# maddomat-master.net
KiCad netlist of a schematic drawn in EAGLE
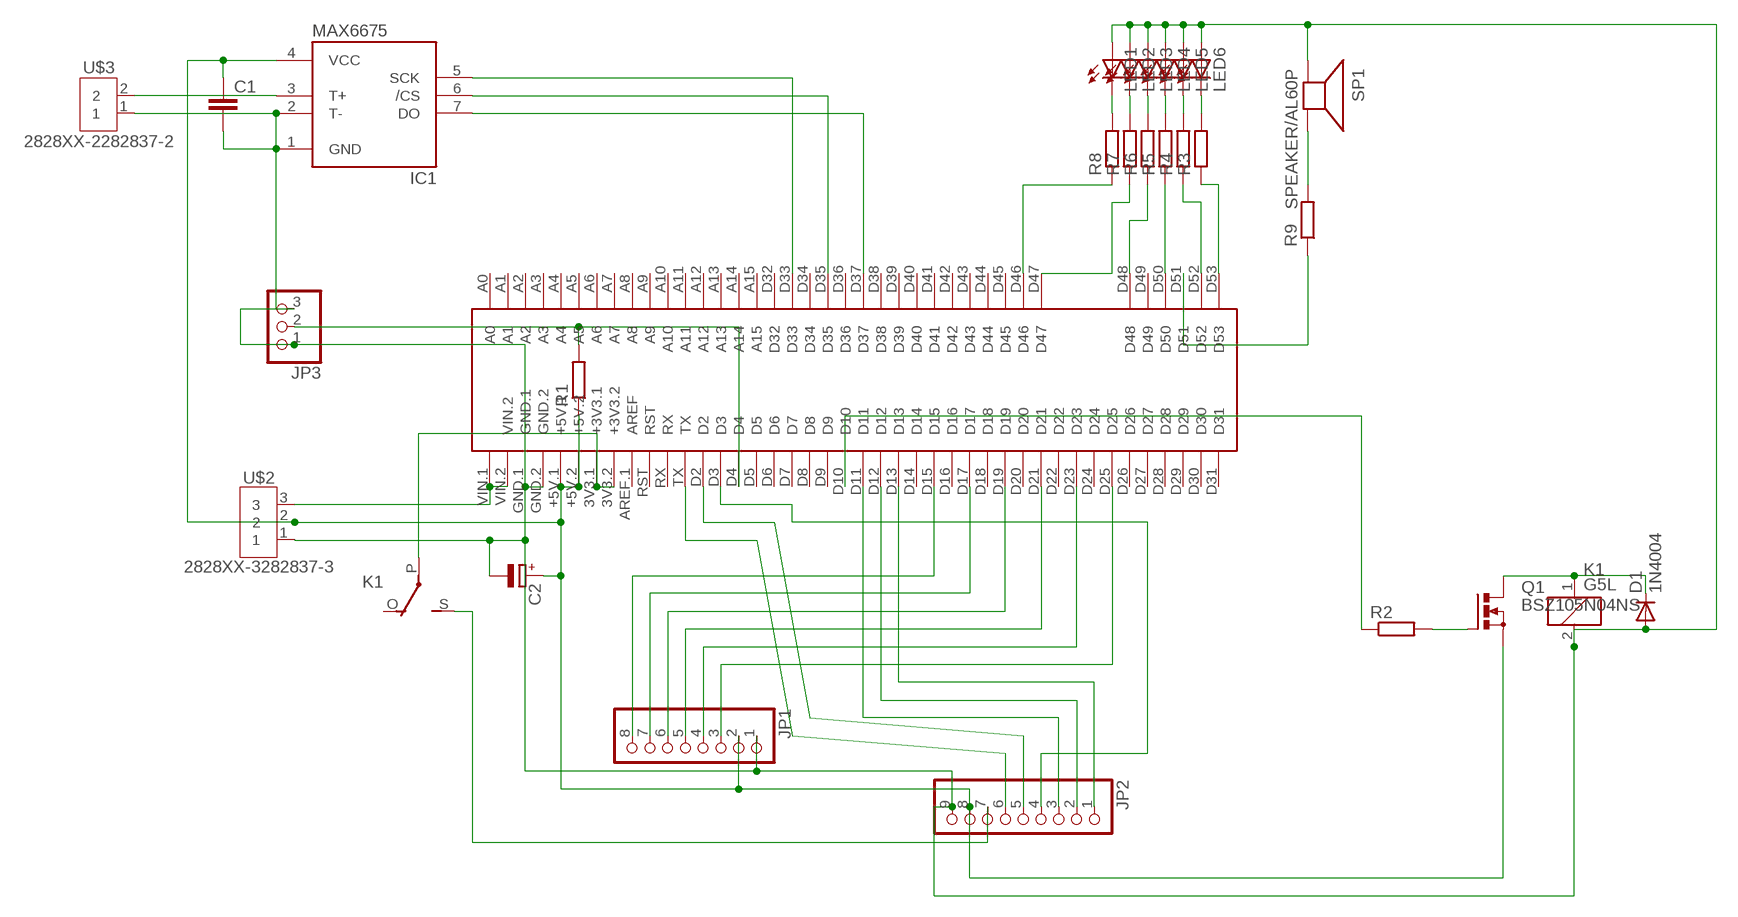
[diagram p0: schematic, sheet 1]

(export (version "E")
  (design (tool "Eeschema 10.0.6"))
  (components
    (comp (ref "C1")
      (value "C-EUC0805")
      (footprint "eagle-import:C0805")
      (libsource (lib "eagle-import") (part "C-EUC0805"))
    )
    (comp (ref "C2")
      (value "CPOL-EUE5-10.5")
      (footprint "eagle-import:E5-10,5")
      (libsource (lib "eagle-import") (part "CPOL-EUE5-10.5"))
    )
    (comp (ref "D1")
      (value "1N4004")
      (footprint "eagle-import:DO41-10")
      (libsource (lib "eagle-import") (part "1N4004"))
    )
    (comp (ref "IC1")
      (value "MAX6675")
      (footprint "eagle-import:SO08")
      (libsource (lib "eagle-import") (part "MAX6675"))
    )
    (comp (ref "JP1")
      (value "PINHD-1X8")
      (footprint "eagle-import:1X08")
      (libsource (lib "eagle-import") (part "PINHD-1X8"))
    )
    (comp (ref "JP2")
      (value "PINHD-1X9")
      (footprint "eagle-import:1X09")
      (libsource (lib "eagle-import") (part "PINHD-1X9"))
    )
    (comp (ref "JP3")
      (value "PINHD-1X3")
      (footprint "eagle-import:1X03")
      (libsource (lib "eagle-import") (part "PINHD-1X3"))
    )
    (comp (ref "K1")
      (value "G5L")
      (footprint "eagle-import:G5LE")
      (libsource (lib "eagle-import") (part "G5L"))
    )
    (comp (ref "LED1")
      (value "LEDCHIP-LED0805")
      (footprint "eagle-import:CHIP-LED0805")
      (libsource (lib "eagle-import") (part "LEDCHIP-LED0805"))
    )
    (comp (ref "LED2")
      (value "LEDCHIP-LED0805")
      (footprint "eagle-import:CHIP-LED0805")
      (libsource (lib "eagle-import") (part "LEDCHIP-LED0805"))
    )
    (comp (ref "LED3")
      (value "LEDCHIP-LED0805")
      (footprint "eagle-import:CHIP-LED0805")
      (libsource (lib "eagle-import") (part "LEDCHIP-LED0805"))
    )
    (comp (ref "LED4")
      (value "LEDCHIP-LED0805")
      (footprint "eagle-import:CHIP-LED0805")
      (libsource (lib "eagle-import") (part "LEDCHIP-LED0805"))
    )
    (comp (ref "LED5")
      (value "LEDCHIP-LED0805")
      (footprint "eagle-import:CHIP-LED0805")
      (libsource (lib "eagle-import") (part "LEDCHIP-LED0805"))
    )
    (comp (ref "LED6")
      (value "LEDCHIP-LED0805")
      (footprint "eagle-import:CHIP-LED0805")
      (libsource (lib "eagle-import") (part "LEDCHIP-LED0805"))
    )
    (comp (ref "Q1")
      (value "BSZ105N04NS")
      (footprint "eagle-import:PG-TDSON-8")
      (libsource (lib "eagle-import") (part "BSZ105N04NS"))
    )
    (comp (ref "R1")
      (value "R-EU_M0805")
      (footprint "eagle-import:M0805")
      (libsource (lib "eagle-import") (part "R-EU_M0805"))
    )
    (comp (ref "R2")
      (value "R-EU_M0805")
      (footprint "eagle-import:M0805")
      (libsource (lib "eagle-import") (part "R-EU_M0805"))
    )
    (comp (ref "R3")
      (value "R-EU_M0805")
      (footprint "eagle-import:M0805")
      (libsource (lib "eagle-import") (part "R-EU_M0805"))
    )
    (comp (ref "R4")
      (value "R-EU_M0805")
      (footprint "eagle-import:M0805")
      (libsource (lib "eagle-import") (part "R-EU_M0805"))
    )
    (comp (ref "R5")
      (value "R-EU_M0805")
      (footprint "eagle-import:M0805")
      (libsource (lib "eagle-import") (part "R-EU_M0805"))
    )
    (comp (ref "R6")
      (value "R-EU_M0805")
      (footprint "eagle-import:M0805")
      (libsource (lib "eagle-import") (part "R-EU_M0805"))
    )
    (comp (ref "R7")
      (value "R-EU_M0805")
      (footprint "eagle-import:M0805")
      (libsource (lib "eagle-import") (part "R-EU_M0805"))
    )
    (comp (ref "R8")
      (value "R-EU_M0805")
      (footprint "eagle-import:M0805")
      (libsource (lib "eagle-import") (part "R-EU_M0805"))
    )
    (comp (ref "R9")
      (value "R-EU_M0805")
      (footprint "eagle-import:M0805")
      (libsource (lib "eagle-import") (part "R-EU_M0805"))
    )
    (comp (ref "SP1")
      (value "SPEAKER/AL60P")
      (footprint "eagle-import:AL60P")
      (libsource (lib "eagle-import") (part "SPEAKER/AL60P"))
    )
    (comp (ref "U$1")
      (value "MEGA2560_MIKRO")
      (footprint "eagle-import:MEGA2560_MIKRO")
      (libsource (lib "eagle-import") (part "MEGA2560_MIKRO"))
    )
    (comp (ref "U$2")
      (value "2828XX-3282837-3")
      (footprint "eagle-import:TERMBLK_508-3N")
      (fields (field (name "MANUFACTURER") "TE Connectivity") (field (name "MPN") "282837-3"))
      (libsource (lib "eagle-import") (part "2828XX-3282837-3"))
    )
    (comp (ref "U$3")
      (value "2828XX-2282837-2")
      (footprint "eagle-import:TERMBLK_508-2N")
      (fields (field (name "MANUFACTURER") "TE Connectivity") (field (name "MPN") "282837-2"))
      (libsource (lib "eagle-import") (part "2828XX-2282837-2"))
    )
  )
  (nets
    (net (code "1") (name "Net-(D1-PadC)") (class "Default")
      (node (ref "D1") (pin "C") (pinfunction "C_C") (pintype "passive"))
      (node (ref "K1") (pin "1") (pinfunction "1_1") (pintype "passive"))
      (node (ref "Q1") (pin "5") (pinfunction "D_5") (pintype "passive"))
      (node (ref "Q1") (pin "6") (pinfunction "D_6") (pintype "passive"))
      (node (ref "Q1") (pin "7") (pinfunction "D_7") (pintype "passive"))
      (node (ref "Q1") (pin "8") (pinfunction "D_8") (pintype "passive"))
      (node (ref "Q1") (pin "TH") (pinfunction "D_TH") (pintype "passive"))
    )
    (net (code "2") (name "Net-(IC1-DO)") (class "Default")
      (node (ref "IC1") (pin "7") (pinfunction "DO_7") (pintype "output"))
      (node (ref "U$1") (pin "D37") (pinfunction "D37_D37") (pintype "bidirectional"))
    )
    (net (code "3") (name "Net-(IC1-GND)") (class "Default")
      (node (ref "C1") (pin "2") (pinfunction "2_2") (pintype "passive"))
      (node (ref "C2") (pin "-") (pinfunction "-_-") (pintype "passive"))
      (node (ref "D1") (pin "A") (pinfunction "A_A") (pintype "passive"))
      (node (ref "IC1") (pin "1") (pinfunction "GND_1") (pintype "power_in"))
      (node (ref "IC1") (pin "2") (pinfunction "T-_2") (pintype "input"))
      (node (ref "JP1") (pin "1") (pinfunction "1_1") (pintype "passive"))
      (node (ref "JP2") (pin "9") (pinfunction "9_9") (pintype "passive"))
      (node (ref "JP3") (pin "1") (pinfunction "1_1") (pintype "passive"))
      (node (ref "JP3") (pin "3") (pinfunction "3_3") (pintype "passive"))
      (node (ref "K1") (pin "2") (pinfunction "2_2") (pintype "passive"))
      (node (ref "LED1") (pin "A") (pinfunction "A_A") (pintype "passive"))
      (node (ref "LED2") (pin "A") (pinfunction "A_A") (pintype "passive"))
      (node (ref "LED3") (pin "A") (pinfunction "A_A") (pintype "passive"))
      (node (ref "LED4") (pin "A") (pinfunction "A_A") (pintype "passive"))
      (node (ref "LED5") (pin "A") (pinfunction "A_A") (pintype "passive"))
      (node (ref "LED6") (pin "A") (pinfunction "A_A") (pintype "passive"))
      (node (ref "SP1") (pin "1") (pinfunction "+_1") (pintype "passive"))
      (node (ref "U$1") (pin "GND.1") (pinfunction "GND.1_GND.1") (pintype "bidirectional"))
      (node (ref "U$1") (pin "GND.2") (pinfunction "GND.2_GND.2") (pintype "bidirectional"))
      (node (ref "U$2") (pin "1") (pinfunction "1_1") (pintype "bidirectional"))
      (node (ref "U$3") (pin "1") (pinfunction "1_1") (pintype "bidirectional"))
    )
    (net (code "4") (name "Net-(IC1-SCK)") (class "Default")
      (node (ref "IC1") (pin "5") (pinfunction "SCK_5") (pintype "input"))
      (node (ref "U$1") (pin "D33") (pinfunction "D33_D33") (pintype "bidirectional"))
    )
    (net (code "5") (name "Net-(IC1-T+)") (class "Default")
      (node (ref "IC1") (pin "3") (pinfunction "T+_3") (pintype "input"))
      (node (ref "U$3") (pin "2") (pinfunction "2_2") (pintype "bidirectional"))
    )
    (net (code "6") (name "Net-(IC1-VCC)") (class "Default")
      (node (ref "C1") (pin "1") (pinfunction "1_1") (pintype "passive"))
      (node (ref "C2") (pin "+") (pinfunction "+_+") (pintype "passive"))
      (node (ref "IC1") (pin "4") (pinfunction "VCC_4") (pintype "power_in"))
      (node (ref "JP1") (pin "2") (pinfunction "2_2") (pintype "passive"))
      (node (ref "JP2") (pin "8") (pinfunction "8_8") (pintype "passive"))
      (node (ref "Q1") (pin "1") (pinfunction "S_1") (pintype "passive"))
      (node (ref "Q1") (pin "2") (pinfunction "S_2") (pintype "passive"))
      (node (ref "Q1") (pin "3") (pinfunction "S_3") (pintype "passive"))
      (node (ref "R1") (pin "1") (pinfunction "1_1") (pintype "passive"))
      (node (ref "U$1") (pin "+5V.1") (pinfunction "+5V.1_+5V.1") (pintype "bidirectional"))
      (node (ref "U$1") (pin "+5V.2") (pinfunction "+5V.2_+5V.2") (pintype "bidirectional"))
      (node (ref "U$2") (pin "2") (pinfunction "2_2") (pintype "bidirectional"))
    )
    (net (code "7") (name "Net-(IC1-{slash}CS)") (class "Default")
      (node (ref "IC1") (pin "6") (pinfunction "/CS_6") (pintype "input"))
      (node (ref "U$1") (pin "D35") (pinfunction "D35_D35") (pintype "bidirectional"))
    )
    (net (code "8") (name "Net-(JP1-Pad3)") (class "Default")
      (node (ref "JP1") (pin "3") (pinfunction "3_3") (pintype "passive"))
      (node (ref "U$1") (pin "D25") (pinfunction "D25_D25") (pintype "bidirectional"))
    )
    (net (code "9") (name "Net-(JP1-Pad4)") (class "Default")
      (node (ref "JP1") (pin "4") (pinfunction "4_4") (pintype "passive"))
      (node (ref "U$1") (pin "D23") (pinfunction "D23_D23") (pintype "bidirectional"))
    )
    (net (code "10") (name "Net-(JP1-Pad5)") (class "Default")
      (node (ref "JP1") (pin "5") (pinfunction "5_5") (pintype "passive"))
      (node (ref "U$1") (pin "D21") (pinfunction "D21_D21") (pintype "bidirectional"))
    )
    (net (code "11") (name "Net-(JP1-Pad6)") (class "Default")
      (node (ref "JP1") (pin "6") (pinfunction "6_6") (pintype "passive"))
      (node (ref "U$1") (pin "D19") (pinfunction "D19_D19") (pintype "bidirectional"))
    )
    (net (code "12") (name "Net-(JP1-Pad7)") (class "Default")
      (node (ref "JP1") (pin "7") (pinfunction "7_7") (pintype "passive"))
      (node (ref "U$1") (pin "D17") (pinfunction "D17_D17") (pintype "bidirectional"))
    )
    (net (code "13") (name "Net-(JP1-Pad8)") (class "Default")
      (node (ref "JP1") (pin "8") (pinfunction "8_8") (pintype "passive"))
      (node (ref "U$1") (pin "D15") (pinfunction "D15_D15") (pintype "bidirectional"))
    )
    (net (code "14") (name "Net-(JP2-Pad1)") (class "Default")
      (node (ref "JP2") (pin "1") (pinfunction "1_1") (pintype "passive"))
      (node (ref "U$1") (pin "D13") (pinfunction "D13_D13") (pintype "bidirectional"))
    )
    (net (code "15") (name "Net-(JP2-Pad2)") (class "Default")
      (node (ref "JP2") (pin "2") (pinfunction "2_2") (pintype "passive"))
      (node (ref "U$1") (pin "D12") (pinfunction "D12_D12") (pintype "bidirectional"))
    )
    (net (code "16") (name "Net-(JP2-Pad3)") (class "Default")
      (node (ref "JP2") (pin "3") (pinfunction "3_3") (pintype "passive"))
      (node (ref "U$1") (pin "D11") (pinfunction "D11_D11") (pintype "bidirectional"))
    )
    (net (code "17") (name "Net-(JP2-Pad4)") (class "Default")
      (node (ref "JP2") (pin "4") (pinfunction "4_4") (pintype "passive"))
      (node (ref "U$1") (pin "D3") (pinfunction "D3_D3") (pintype "bidirectional"))
    )
    (net (code "18") (name "Net-(JP2-Pad5)") (class "Default")
      (node (ref "JP2") (pin "5") (pinfunction "5_5") (pintype "passive"))
      (node (ref "U$1") (pin "D2") (pinfunction "D2_D2") (pintype "bidirectional"))
    )
    (net (code "19") (name "Net-(JP2-Pad6)") (class "Default")
      (node (ref "JP2") (pin "6") (pinfunction "6_6") (pintype "passive"))
      (node (ref "U$1") (pin "TX") (pinfunction "TX_TX") (pintype "bidirectional"))
    )
    (net (code "20") (name "Net-(JP2-Pad7)") (class "Default")
      (node (ref "JP2") (pin "7") (pinfunction "7_7") (pintype "passive"))
      (node (ref "K1") (pin "S") (pinfunction "S_S") (pintype "passive"))
    )
    (net (code "21") (name "Net-(JP3-Pad2)") (class "Default")
      (node (ref "JP3") (pin "2") (pinfunction "2_2") (pintype "passive"))
      (node (ref "R1") (pin "2") (pinfunction "2_2") (pintype "passive"))
      (node (ref "U$1") (pin "D4") (pinfunction "D4_D4") (pintype "bidirectional"))
    )
    (net (code "22") (name "Net-(LED1-PadC)") (class "Default")
      (node (ref "LED1") (pin "C") (pinfunction "C_C") (pintype "passive"))
      (node (ref "R8") (pin "2") (pinfunction "2_2") (pintype "passive"))
    )
    (net (code "23") (name "Net-(LED2-PadC)") (class "Default")
      (node (ref "LED2") (pin "C") (pinfunction "C_C") (pintype "passive"))
      (node (ref "R7") (pin "2") (pinfunction "2_2") (pintype "passive"))
    )
    (net (code "24") (name "Net-(LED3-PadC)") (class "Default")
      (node (ref "LED3") (pin "C") (pinfunction "C_C") (pintype "passive"))
      (node (ref "R6") (pin "2") (pinfunction "2_2") (pintype "passive"))
    )
    (net (code "25") (name "Net-(LED4-PadC)") (class "Default")
      (node (ref "LED4") (pin "C") (pinfunction "C_C") (pintype "passive"))
      (node (ref "R5") (pin "2") (pinfunction "2_2") (pintype "passive"))
    )
    (net (code "26") (name "Net-(LED5-PadC)") (class "Default")
      (node (ref "LED5") (pin "C") (pinfunction "C_C") (pintype "passive"))
      (node (ref "R4") (pin "2") (pinfunction "2_2") (pintype "passive"))
    )
    (net (code "27") (name "Net-(LED6-PadC)") (class "Default")
      (node (ref "LED6") (pin "C") (pinfunction "C_C") (pintype "passive"))
      (node (ref "R3") (pin "2") (pinfunction "2_2") (pintype "passive"))
    )
    (net (code "28") (name "Net-(Q1-G)") (class "Default")
      (node (ref "Q1") (pin "4") (pinfunction "G_4") (pintype "passive"))
      (node (ref "R2") (pin "2") (pinfunction "2_2") (pintype "passive"))
    )
    (net (code "29") (name "Net-(R2-Pad1)") (class "Default")
      (node (ref "R2") (pin "1") (pinfunction "1_1") (pintype "passive"))
      (node (ref "U$1") (pin "D10") (pinfunction "D10_D10") (pintype "bidirectional"))
    )
    (net (code "30") (name "Net-(R3-Pad1)") (class "Default")
      (node (ref "R3") (pin "1") (pinfunction "1_1") (pintype "passive"))
      (node (ref "U$1") (pin "D53") (pinfunction "D53_D53") (pintype "bidirectional"))
    )
    (net (code "31") (name "Net-(R4-Pad1)") (class "Default")
      (node (ref "R4") (pin "1") (pinfunction "1_1") (pintype "passive"))
      (node (ref "U$1") (pin "D52") (pinfunction "D52_D52") (pintype "bidirectional"))
    )
    (net (code "32") (name "Net-(R5-Pad1)") (class "Default")
      (node (ref "R5") (pin "1") (pinfunction "1_1") (pintype "passive"))
      (node (ref "U$1") (pin "D50") (pinfunction "D50_D50") (pintype "bidirectional"))
    )
    (net (code "33") (name "Net-(R6-Pad1)") (class "Default")
      (node (ref "R6") (pin "1") (pinfunction "1_1") (pintype "passive"))
      (node (ref "U$1") (pin "D48") (pinfunction "D48_D48") (pintype "bidirectional"))
    )
    (net (code "34") (name "Net-(R7-Pad1)") (class "Default")
      (node (ref "R7") (pin "1") (pinfunction "1_1") (pintype "passive"))
      (node (ref "U$1") (pin "D47") (pinfunction "D47_D47") (pintype "bidirectional"))
    )
    (net (code "35") (name "Net-(R8-Pad1)") (class "Default")
      (node (ref "R8") (pin "1") (pinfunction "1_1") (pintype "passive"))
      (node (ref "U$1") (pin "D46") (pinfunction "D46_D46") (pintype "bidirectional"))
    )
    (net (code "36") (name "Net-(R9-Pad1)") (class "Default")
      (node (ref "R9") (pin "1") (pinfunction "1_1") (pintype "passive"))
      (node (ref "U$1") (pin "D51") (pinfunction "D51_D51") (pintype "bidirectional"))
    )
    (net (code "37") (name "Net-(SP1--)") (class "Default")
      (node (ref "R9") (pin "2") (pinfunction "2_2") (pintype "passive"))
      (node (ref "SP1") (pin "2") (pinfunction "-_2") (pintype "passive"))
    )
    (net (code "38") (name "Net-(U$1-+3V3.1)") (class "Default")
      (node (ref "K1") (pin "P") (pinfunction "P_P") (pintype "passive"))
      (node (ref "U$1") (pin "3V3.1") (pinfunction "+3V3.1_3V3.1") (pintype "bidirectional"))
      (node (ref "U$1") (pin "3V3.2") (pinfunction "+3V3.2_3V3.2") (pintype "bidirectional"))
    )
    (net (code "39") (name "Net-(U$1-PadVIN.1)") (class "Default")
      (node (ref "U$1") (pin "VIN.1") (pinfunction "VIN.1_VIN.1") (pintype "bidirectional"))
      (node (ref "U$1") (pin "VIN.2") (pinfunction "VIN.2_VIN.2") (pintype "bidirectional"))
      (node (ref "U$2") (pin "3") (pinfunction "3_3") (pintype "bidirectional"))
    )
    (net (code "40") (name "unconnected-(K1-PadO)") (class "Default")
      (node (ref "K1") (pin "O") (pinfunction "O_O") (pintype "passive"))
    )
    (net (code "41") (name "unconnected-(U$1-AREF-PadAREF.1)") (class "Default")
      (node (ref "U$1") (pin "AREF.1") (pinfunction "AREF_AREF.1") (pintype "bidirectional"))
    )
    (net (code "42") (name "unconnected-(U$1-PadA0)") (class "Default")
      (node (ref "U$1") (pin "A0") (pinfunction "A0_A0") (pintype "bidirectional"))
    )
    (net (code "43") (name "unconnected-(U$1-PadA1)") (class "Default")
      (node (ref "U$1") (pin "A1") (pinfunction "A1_A1") (pintype "bidirectional"))
    )
    (net (code "44") (name "unconnected-(U$1-PadA2)") (class "Default")
      (node (ref "U$1") (pin "A2") (pinfunction "A2_A2") (pintype "bidirectional"))
    )
    (net (code "45") (name "unconnected-(U$1-PadA3)") (class "Default")
      (node (ref "U$1") (pin "A3") (pinfunction "A3_A3") (pintype "bidirectional"))
    )
    (net (code "46") (name "unconnected-(U$1-PadA4)") (class "Default")
      (node (ref "U$1") (pin "A4") (pinfunction "A4_A4") (pintype "bidirectional"))
    )
    (net (code "47") (name "unconnected-(U$1-PadA5)") (class "Default")
      (node (ref "U$1") (pin "A5") (pinfunction "A5_A5") (pintype "bidirectional"))
    )
    (net (code "48") (name "unconnected-(U$1-PadA6)") (class "Default")
      (node (ref "U$1") (pin "A6") (pinfunction "A6_A6") (pintype "bidirectional"))
    )
    (net (code "49") (name "unconnected-(U$1-PadA7)") (class "Default")
      (node (ref "U$1") (pin "A7") (pinfunction "A7_A7") (pintype "bidirectional"))
    )
    (net (code "50") (name "unconnected-(U$1-PadA8)") (class "Default")
      (node (ref "U$1") (pin "A8") (pinfunction "A8_A8") (pintype "bidirectional"))
    )
    (net (code "51") (name "unconnected-(U$1-PadA9)") (class "Default")
      (node (ref "U$1") (pin "A9") (pinfunction "A9_A9") (pintype "bidirectional"))
    )
    (net (code "52") (name "unconnected-(U$1-PadA10)") (class "Default")
      (node (ref "U$1") (pin "A10") (pinfunction "A10_A10") (pintype "bidirectional"))
    )
    (net (code "53") (name "unconnected-(U$1-PadA11)") (class "Default")
      (node (ref "U$1") (pin "A11") (pinfunction "A11_A11") (pintype "bidirectional"))
    )
    (net (code "54") (name "unconnected-(U$1-PadA12)") (class "Default")
      (node (ref "U$1") (pin "A12") (pinfunction "A12_A12") (pintype "bidirectional"))
    )
    (net (code "55") (name "unconnected-(U$1-PadA13)") (class "Default")
      (node (ref "U$1") (pin "A13") (pinfunction "A13_A13") (pintype "bidirectional"))
    )
    (net (code "56") (name "unconnected-(U$1-PadA14)") (class "Default")
      (node (ref "U$1") (pin "A14") (pinfunction "A14_A14") (pintype "bidirectional"))
    )
    (net (code "57") (name "unconnected-(U$1-PadA15)") (class "Default")
      (node (ref "U$1") (pin "A15") (pinfunction "A15_A15") (pintype "bidirectional"))
    )
    (net (code "58") (name "unconnected-(U$1-PadD5)") (class "Default")
      (node (ref "U$1") (pin "D5") (pinfunction "D5_D5") (pintype "bidirectional"))
    )
    (net (code "59") (name "unconnected-(U$1-PadD6)") (class "Default")
      (node (ref "U$1") (pin "D6") (pinfunction "D6_D6") (pintype "bidirectional"))
    )
    (net (code "60") (name "unconnected-(U$1-PadD7)") (class "Default")
      (node (ref "U$1") (pin "D7") (pinfunction "D7_D7") (pintype "bidirectional"))
    )
    (net (code "61") (name "unconnected-(U$1-PadD8)") (class "Default")
      (node (ref "U$1") (pin "D8") (pinfunction "D8_D8") (pintype "bidirectional"))
    )
    (net (code "62") (name "unconnected-(U$1-PadD9)") (class "Default")
      (node (ref "U$1") (pin "D9") (pinfunction "D9_D9") (pintype "bidirectional"))
    )
    (net (code "63") (name "unconnected-(U$1-PadD14)") (class "Default")
      (node (ref "U$1") (pin "D14") (pinfunction "D14_D14") (pintype "bidirectional"))
    )
    (net (code "64") (name "unconnected-(U$1-PadD16)") (class "Default")
      (node (ref "U$1") (pin "D16") (pinfunction "D16_D16") (pintype "bidirectional"))
    )
    (net (code "65") (name "unconnected-(U$1-PadD18)") (class "Default")
      (node (ref "U$1") (pin "D18") (pinfunction "D18_D18") (pintype "bidirectional"))
    )
    (net (code "66") (name "unconnected-(U$1-PadD20)") (class "Default")
      (node (ref "U$1") (pin "D20") (pinfunction "D20_D20") (pintype "bidirectional"))
    )
    (net (code "67") (name "unconnected-(U$1-PadD22)") (class "Default")
      (node (ref "U$1") (pin "D22") (pinfunction "D22_D22") (pintype "bidirectional"))
    )
    (net (code "68") (name "unconnected-(U$1-PadD24)") (class "Default")
      (node (ref "U$1") (pin "D24") (pinfunction "D24_D24") (pintype "bidirectional"))
    )
    (net (code "69") (name "unconnected-(U$1-PadD26)") (class "Default")
      (node (ref "U$1") (pin "D26") (pinfunction "D26_D26") (pintype "bidirectional"))
    )
    (net (code "70") (name "unconnected-(U$1-PadD27)") (class "Default")
      (node (ref "U$1") (pin "D27") (pinfunction "D27_D27") (pintype "bidirectional"))
    )
    (net (code "71") (name "unconnected-(U$1-PadD28)") (class "Default")
      (node (ref "U$1") (pin "D28") (pinfunction "D28_D28") (pintype "bidirectional"))
    )
    (net (code "72") (name "unconnected-(U$1-PadD29)") (class "Default")
      (node (ref "U$1") (pin "D29") (pinfunction "D29_D29") (pintype "bidirectional"))
    )
    (net (code "73") (name "unconnected-(U$1-PadD30)") (class "Default")
      (node (ref "U$1") (pin "D30") (pinfunction "D30_D30") (pintype "bidirectional"))
    )
    (net (code "74") (name "unconnected-(U$1-PadD31)") (class "Default")
      (node (ref "U$1") (pin "D31") (pinfunction "D31_D31") (pintype "bidirectional"))
    )
    (net (code "75") (name "unconnected-(U$1-PadD32)") (class "Default")
      (node (ref "U$1") (pin "D32") (pinfunction "D32_D32") (pintype "bidirectional"))
    )
    (net (code "76") (name "unconnected-(U$1-PadD34)") (class "Default")
      (node (ref "U$1") (pin "D34") (pinfunction "D34_D34") (pintype "bidirectional"))
    )
    (net (code "77") (name "unconnected-(U$1-PadD36)") (class "Default")
      (node (ref "U$1") (pin "D36") (pinfunction "D36_D36") (pintype "bidirectional"))
    )
    (net (code "78") (name "unconnected-(U$1-PadD38)") (class "Default")
      (node (ref "U$1") (pin "D38") (pinfunction "D38_D38") (pintype "bidirectional"))
    )
    (net (code "79") (name "unconnected-(U$1-PadD39)") (class "Default")
      (node (ref "U$1") (pin "D39") (pinfunction "D39_D39") (pintype "bidirectional"))
    )
    (net (code "80") (name "unconnected-(U$1-PadD40)") (class "Default")
      (node (ref "U$1") (pin "D40") (pinfunction "D40_D40") (pintype "bidirectional"))
    )
    (net (code "81") (name "unconnected-(U$1-PadD41)") (class "Default")
      (node (ref "U$1") (pin "D41") (pinfunction "D41_D41") (pintype "bidirectional"))
    )
    (net (code "82") (name "unconnected-(U$1-PadD42)") (class "Default")
      (node (ref "U$1") (pin "D42") (pinfunction "D42_D42") (pintype "bidirectional"))
    )
    (net (code "83") (name "unconnected-(U$1-PadD43)") (class "Default")
      (node (ref "U$1") (pin "D43") (pinfunction "D43_D43") (pintype "bidirectional"))
    )
    (net (code "84") (name "unconnected-(U$1-PadD44)") (class "Default")
      (node (ref "U$1") (pin "D44") (pinfunction "D44_D44") (pintype "bidirectional"))
    )
    (net (code "85") (name "unconnected-(U$1-PadD45)") (class "Default")
      (node (ref "U$1") (pin "D45") (pinfunction "D45_D45") (pintype "bidirectional"))
    )
    (net (code "86") (name "unconnected-(U$1-PadD49)") (class "Default")
      (node (ref "U$1") (pin "D49") (pinfunction "D49_D49") (pintype "bidirectional"))
    )
    (net (code "87") (name "unconnected-(U$1-PadRST)") (class "Default")
      (node (ref "U$1") (pin "RST") (pinfunction "RST_RST") (pintype "bidirectional"))
    )
    (net (code "88") (name "unconnected-(U$1-PadRX)") (class "Default")
      (node (ref "U$1") (pin "RX") (pinfunction "RX_RX") (pintype "bidirectional"))
    )
  )
)
